# QCopterFC_MCU_Sch.net
KiCad netlist of a schematic drawn in Altium Designer
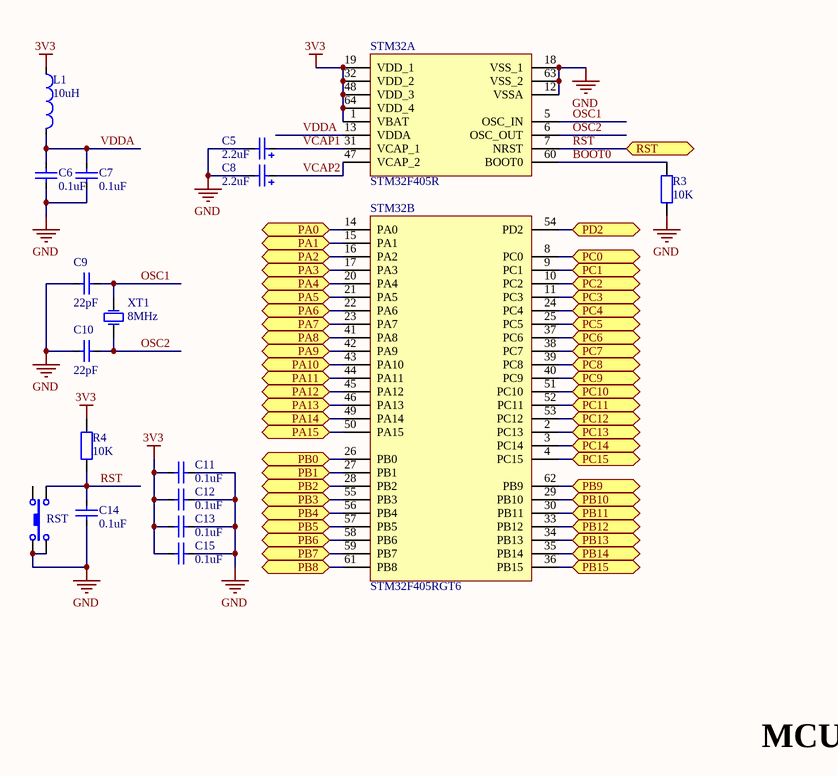
[diagram p0: QCopterFC_MCU_Sch.SchDoc]

(export (version "E")
  (design (tool "Eeschema 10.0.6"))
  (components
    (comp (ref "C5")
      (value "2.2uF")
      (footprint "PCB_Passive:CAP_TAN_P0805")
      (description "Capacitor")
      (fields (field (name "Comment") "Cap_Tan_0805"))
      (libsource (lib "SCH_Passive") (part "Cap_Tan_0805"))
    )
    (comp (ref "C6")
      (value "0.1uF")
      (footprint "PCB_Passive:CAP_0603")
      (description "Capacitor")
      (fields (field (name "Comment") "Cap_0603"))
      (libsource (lib "SCH_Passive") (part "Cap_0603"))
    )
    (comp (ref "C7")
      (value "0.1uF")
      (footprint "PCB_Passive:CAP_0603")
      (description "Capacitor")
      (fields (field (name "Comment") "Cap_0603"))
      (libsource (lib "SCH_Passive") (part "Cap_0603"))
    )
    (comp (ref "C8")
      (value "2.2uF")
      (footprint "PCB_Passive:CAP_TAN_P0805")
      (description "Capacitor")
      (fields (field (name "Comment") "Cap_Tan_0805"))
      (libsource (lib "SCH_Passive") (part "Cap_Tan_0805"))
    )
    (comp (ref "C9")
      (value "22pF")
      (footprint "PCB_Passive:CAP_0603")
      (description "Capacitor")
      (fields (field (name "Comment") "Cap_0603"))
      (libsource (lib "SCH_Passive") (part "Cap_0603"))
    )
    (comp (ref "C10")
      (value "22pF")
      (footprint "PCB_Passive:CAP_0603")
      (description "Capacitor")
      (fields (field (name "Comment") "Cap_0603"))
      (libsource (lib "SCH_Passive") (part "Cap_0603"))
    )
    (comp (ref "C11")
      (value "0.1uF")
      (footprint "PCB_Passive:CAP_0603")
      (description "Capacitor")
      (fields (field (name "Comment") "Cap_0603"))
      (libsource (lib "SCH_Passive") (part "Cap_0603"))
    )
    (comp (ref "C12")
      (value "0.1uF")
      (footprint "PCB_Passive:CAP_0603")
      (description "Capacitor")
      (fields (field (name "Comment") "Cap_0603"))
      (libsource (lib "SCH_Passive") (part "Cap_0603"))
    )
    (comp (ref "C13")
      (value "0.1uF")
      (footprint "PCB_Passive:CAP_0603")
      (description "Capacitor")
      (fields (field (name "Comment") "Cap_0603"))
      (libsource (lib "SCH_Passive") (part "Cap_0603"))
    )
    (comp (ref "C14")
      (value "0.1uF")
      (footprint "PCB_Passive:CAP_0603")
      (description "Capacitor")
      (fields (field (name "Comment") "Cap_0603"))
      (libsource (lib "SCH_Passive") (part "Cap_0603"))
    )
    (comp (ref "C15")
      (value "0.1uF")
      (footprint "PCB_Passive:CAP_0603")
      (description "Capacitor")
      (fields (field (name "Comment") "Cap_0603"))
      (libsource (lib "SCH_Passive") (part "Cap_0603"))
    )
    (comp (ref "L1")
      (value "10uH")
      (footprint "PCB_Passive:IND_0603")
      (description "Inductor")
      (fields (field (name "Comment") "Ind_0603"))
      (libsource (lib "SCH_Passive") (part "Ind_0603"))
    )
    (comp (ref "R3")
      (value "10K")
      (footprint "PCB_Passive:RES_0603")
      (description "Resistor")
      (fields (field (name "Comment") "Res_0603"))
      (libsource (lib "SCH_Passive") (part "Res_0603"))
    )
    (comp (ref "R4")
      (value "10K")
      (footprint "PCB_Passive:RES_0603")
      (description "Resistor")
      (fields (field (name "Comment") "Res_0603"))
      (libsource (lib "SCH_Passive") (part "Res_0603"))
    )
    (comp (ref "RST")
      (value "BT_TACT_4.2x6.4_90")
      (footprint "PCB_Switch:BT_TACT_4.2x6.4_90")
      (description "Switch")
      (libsource (lib "SCH_Switch") (part "BT_TACT_4.2x6.4_90"))
    )
    (comp (ref "STM32")
      (value "STM32F405R")
      (footprint "PCB_IC:STM32F_64")
      (description "MCU")
      (libsource (lib "") (part "STM32F405R_1"))
    )
    (comp (ref "XT1")
      (value "8MHz")
      (footprint "PCB_Oscillator:XTAL_5032")
      (description "Crystal Oscillator")
      (fields (field (name "Comment") "XTAL_5032") (field (name "PUBLISHER") "Altium Limited"))
      (libsource (lib "SCH_Oscillator") (part "XTAL_5032"))
    )
  )
  (nets
    (net (code "1") (name "/BOOT0") (class "Default")
      (node (ref "R3") (pin "1") (pinfunction "1_1") (pintype "passive"))
      (node (ref "STM32") (pin "60") (pinfunction "BOOT0_60") (pintype "passive"))
    )
    (net (code "2") (name "/OSC1") (class "Default")
      (node (ref "C9") (pin "2") (pinfunction "2_2") (pintype "passive"))
      (node (ref "STM32") (pin "5") (pinfunction "OSC_IN_5") (pintype "passive"))
      (node (ref "XT1") (pin "2") (pinfunction "OSC2_2") (pintype "passive"))
    )
    (net (code "3") (name "/OSC2") (class "Default")
      (node (ref "C10") (pin "2") (pinfunction "2_2") (pintype "passive"))
      (node (ref "STM32") (pin "6") (pinfunction "OSC_OUT_6") (pintype "passive"))
      (node (ref "XT1") (pin "1") (pinfunction "OSC1_1") (pintype "passive"))
    )
    (net (code "4") (name "/PA0") (class "Default")
      (node (ref "STM32") (pin "14") (pinfunction "PA0_14") (pintype "passive"))
    )
    (net (code "5") (name "/PA1") (class "Default")
      (node (ref "STM32") (pin "15") (pinfunction "PA1_15") (pintype "passive"))
    )
    (net (code "6") (name "/PA2") (class "Default")
      (node (ref "STM32") (pin "16") (pinfunction "PA2_16") (pintype "passive"))
    )
    (net (code "7") (name "/PA3") (class "Default")
      (node (ref "STM32") (pin "17") (pinfunction "PA3_17") (pintype "passive"))
    )
    (net (code "8") (name "/PA4") (class "Default")
      (node (ref "STM32") (pin "20") (pinfunction "PA4_20") (pintype "passive"))
    )
    (net (code "9") (name "/PA5") (class "Default")
      (node (ref "STM32") (pin "21") (pinfunction "PA5_21") (pintype "passive"))
    )
    (net (code "10") (name "/PA6") (class "Default")
      (node (ref "STM32") (pin "22") (pinfunction "PA6_22") (pintype "passive"))
    )
    (net (code "11") (name "/PA7") (class "Default")
      (node (ref "STM32") (pin "23") (pinfunction "PA7_23") (pintype "passive"))
    )
    (net (code "12") (name "/PA8") (class "Default")
      (node (ref "STM32") (pin "41") (pinfunction "PA8_41") (pintype "passive"))
    )
    (net (code "13") (name "/PA9") (class "Default")
      (node (ref "STM32") (pin "42") (pinfunction "PA9_42") (pintype "passive"))
    )
    (net (code "14") (name "/PA10") (class "Default")
      (node (ref "STM32") (pin "43") (pinfunction "PA10_43") (pintype "passive"))
    )
    (net (code "15") (name "/PA11") (class "Default")
      (node (ref "STM32") (pin "44") (pinfunction "PA11_44") (pintype "passive"))
    )
    (net (code "16") (name "/PA12") (class "Default")
      (node (ref "STM32") (pin "45") (pinfunction "PA12_45") (pintype "passive"))
    )
    (net (code "17") (name "/PA13") (class "Default")
      (node (ref "STM32") (pin "46") (pinfunction "PA13_46") (pintype "passive"))
    )
    (net (code "18") (name "/PA14") (class "Default")
      (node (ref "STM32") (pin "49") (pinfunction "PA14_49") (pintype "passive"))
    )
    (net (code "19") (name "/PA15") (class "Default")
      (node (ref "STM32") (pin "50") (pinfunction "PA15_50") (pintype "passive"))
    )
    (net (code "20") (name "/PB0") (class "Default")
      (node (ref "STM32") (pin "26") (pinfunction "PB0_26") (pintype "passive"))
    )
    (net (code "21") (name "/PB1") (class "Default")
      (node (ref "STM32") (pin "27") (pinfunction "PB1_27") (pintype "passive"))
    )
    (net (code "22") (name "/PB2") (class "Default")
      (node (ref "STM32") (pin "28") (pinfunction "PB2_28") (pintype "passive"))
    )
    (net (code "23") (name "/PB3") (class "Default")
      (node (ref "STM32") (pin "55") (pinfunction "PB3_55") (pintype "passive"))
    )
    (net (code "24") (name "/PB4") (class "Default")
      (node (ref "STM32") (pin "56") (pinfunction "PB4_56") (pintype "passive"))
    )
    (net (code "25") (name "/PB5") (class "Default")
      (node (ref "STM32") (pin "57") (pinfunction "PB5_57") (pintype "passive"))
    )
    (net (code "26") (name "/PB6") (class "Default")
      (node (ref "STM32") (pin "58") (pinfunction "PB6_58") (pintype "passive"))
    )
    (net (code "27") (name "/PB7") (class "Default")
      (node (ref "STM32") (pin "59") (pinfunction "PB7_59") (pintype "passive"))
    )
    (net (code "28") (name "/PB8") (class "Default")
      (node (ref "STM32") (pin "61") (pinfunction "PB8_61") (pintype "passive"))
    )
    (net (code "29") (name "/PB9") (class "Default")
      (node (ref "STM32") (pin "62") (pinfunction "PB9_62") (pintype "passive"))
    )
    (net (code "30") (name "/PB10") (class "Default")
      (node (ref "STM32") (pin "29") (pinfunction "PB10_29") (pintype "passive"))
    )
    (net (code "31") (name "/PB11") (class "Default")
      (node (ref "STM32") (pin "30") (pinfunction "PB11_30") (pintype "passive"))
    )
    (net (code "32") (name "/PB12") (class "Default")
      (node (ref "STM32") (pin "33") (pinfunction "PB12_33") (pintype "passive"))
    )
    (net (code "33") (name "/PB13") (class "Default")
      (node (ref "STM32") (pin "34") (pinfunction "PB13_34") (pintype "passive"))
    )
    (net (code "34") (name "/PB14") (class "Default")
      (node (ref "STM32") (pin "35") (pinfunction "PB14_35") (pintype "passive"))
    )
    (net (code "35") (name "/PB15") (class "Default")
      (node (ref "STM32") (pin "36") (pinfunction "PB15_36") (pintype "passive"))
    )
    (net (code "36") (name "/PC0") (class "Default")
      (node (ref "STM32") (pin "8") (pinfunction "PC0_8") (pintype "passive"))
    )
    (net (code "37") (name "/PC1") (class "Default")
      (node (ref "STM32") (pin "9") (pinfunction "PC1_9") (pintype "passive"))
    )
    (net (code "38") (name "/PC2") (class "Default")
      (node (ref "STM32") (pin "10") (pinfunction "PC2_10") (pintype "passive"))
    )
    (net (code "39") (name "/PC3") (class "Default")
      (node (ref "STM32") (pin "11") (pinfunction "PC3_11") (pintype "passive"))
    )
    (net (code "40") (name "/PC4") (class "Default")
      (node (ref "STM32") (pin "24") (pinfunction "PC4_24") (pintype "passive"))
    )
    (net (code "41") (name "/PC5") (class "Default")
      (node (ref "STM32") (pin "25") (pinfunction "PC5_25") (pintype "passive"))
    )
    (net (code "42") (name "/PC6") (class "Default")
      (node (ref "STM32") (pin "37") (pinfunction "PC6_37") (pintype "passive"))
    )
    (net (code "43") (name "/PC7") (class "Default")
      (node (ref "STM32") (pin "38") (pinfunction "PC7_38") (pintype "passive"))
    )
    (net (code "44") (name "/PC8") (class "Default")
      (node (ref "STM32") (pin "39") (pinfunction "PC8_39") (pintype "passive"))
    )
    (net (code "45") (name "/PC9") (class "Default")
      (node (ref "STM32") (pin "40") (pinfunction "PC9_40") (pintype "passive"))
    )
    (net (code "46") (name "/PC10") (class "Default")
      (node (ref "STM32") (pin "51") (pinfunction "PC10_51") (pintype "passive"))
    )
    (net (code "47") (name "/PC11") (class "Default")
      (node (ref "STM32") (pin "52") (pinfunction "PC11_52") (pintype "passive"))
    )
    (net (code "48") (name "/PC12") (class "Default")
      (node (ref "STM32") (pin "53") (pinfunction "PC12_53") (pintype "passive"))
    )
    (net (code "49") (name "/PC13") (class "Default")
      (node (ref "STM32") (pin "2") (pinfunction "PC13_2") (pintype "passive"))
    )
    (net (code "50") (name "/PC14") (class "Default")
      (node (ref "STM32") (pin "3") (pinfunction "PC14_3") (pintype "passive"))
    )
    (net (code "51") (name "/PC15") (class "Default")
      (node (ref "STM32") (pin "4") (pinfunction "PC15_4") (pintype "passive"))
    )
    (net (code "52") (name "/PD2") (class "Default")
      (node (ref "STM32") (pin "54") (pinfunction "PD2_54") (pintype "passive"))
    )
    (net (code "53") (name "/RST") (class "Default")
      (node (ref "C14") (pin "1") (pinfunction "1_1") (pintype "passive"))
      (node (ref "R4") (pin "2") (pinfunction "2_2") (pintype "passive"))
      (node (ref "RST") (pin "4") (pinfunction "4_4") (pintype "passive"))
      (node (ref "STM32") (pin "7") (pinfunction "NRST_7") (pintype "passive"))
    )
    (net (code "54") (name "/VCAP1") (class "Default")
      (node (ref "C5") (pin "1") (pinfunction "1_1") (pintype "passive"))
      (node (ref "STM32") (pin "31") (pinfunction "VCAP_1_31") (pintype "passive"))
    )
    (net (code "55") (name "/VCAP2") (class "Default")
      (node (ref "C8") (pin "1") (pinfunction "1_1") (pintype "passive"))
      (node (ref "STM32") (pin "47") (pinfunction "VCAP_2_47") (pintype "passive"))
    )
    (net (code "56") (name "/VDDA") (class "Default")
      (node (ref "C6") (pin "1") (pinfunction "1_1") (pintype "passive"))
      (node (ref "C7") (pin "1") (pinfunction "1_1") (pintype "passive"))
      (node (ref "L1") (pin "2") (pinfunction "2_2") (pintype "passive"))
      (node (ref "STM32") (pin "13") (pinfunction "VDDA_13") (pintype "passive"))
    )
    (net (code "57") (name "3V3") (class "Default")
      (node (ref "C11") (pin "2") (pinfunction "2_2") (pintype "passive"))
      (node (ref "C12") (pin "2") (pinfunction "2_2") (pintype "passive"))
      (node (ref "C13") (pin "2") (pinfunction "2_2") (pintype "passive"))
      (node (ref "C15") (pin "2") (pinfunction "2_2") (pintype "passive"))
      (node (ref "L1") (pin "1") (pinfunction "1_1") (pintype "passive"))
      (node (ref "R4") (pin "1") (pinfunction "1_1") (pintype "passive"))
      (node (ref "STM32") (pin "1") (pinfunction "VBAT_1") (pintype "passive"))
      (node (ref "STM32") (pin "19") (pinfunction "VDD_1_19") (pintype "passive"))
      (node (ref "STM32") (pin "32") (pinfunction "VDD_2_32") (pintype "passive"))
      (node (ref "STM32") (pin "48") (pinfunction "VDD_3_48") (pintype "passive"))
      (node (ref "STM32") (pin "64") (pinfunction "VDD_4_64") (pintype "passive"))
    )
    (net (code "58") (name "GND") (class "Default")
      (node (ref "C10") (pin "1") (pinfunction "1_1") (pintype "passive"))
      (node (ref "C11") (pin "1") (pinfunction "1_1") (pintype "passive"))
      (node (ref "C12") (pin "1") (pinfunction "1_1") (pintype "passive"))
      (node (ref "C13") (pin "1") (pinfunction "1_1") (pintype "passive"))
      (node (ref "C14") (pin "2") (pinfunction "2_2") (pintype "passive"))
      (node (ref "C15") (pin "1") (pinfunction "1_1") (pintype "passive"))
      (node (ref "C5") (pin "2") (pinfunction "2_2") (pintype "passive"))
      (node (ref "C6") (pin "2") (pinfunction "2_2") (pintype "passive"))
      (node (ref "C7") (pin "2") (pinfunction "2_2") (pintype "passive"))
      (node (ref "C8") (pin "2") (pinfunction "2_2") (pintype "passive"))
      (node (ref "C9") (pin "1") (pinfunction "1_1") (pintype "passive"))
      (node (ref "R3") (pin "2") (pinfunction "2_2") (pintype "passive"))
      (node (ref "RST") (pin "1") (pinfunction "1_1") (pintype "passive"))
      (node (ref "RST") (pin "3") (pinfunction "3_3") (pintype "passive"))
      (node (ref "STM32") (pin "12") (pinfunction "VSSA_12") (pintype "passive"))
      (node (ref "STM32") (pin "18") (pinfunction "VSS_1_18") (pintype "passive"))
      (node (ref "STM32") (pin "63") (pinfunction "VSS_2_63") (pintype "passive"))
    )
    (net (code "59") (name "unconnected-(RST-Pad2)") (class "Default")
      (node (ref "RST") (pin "2") (pinfunction "2_2") (pintype "passive"))
    )
  )
)
